# a78-flashcart.net
KiCad netlist of a schematic drawn in EAGLE
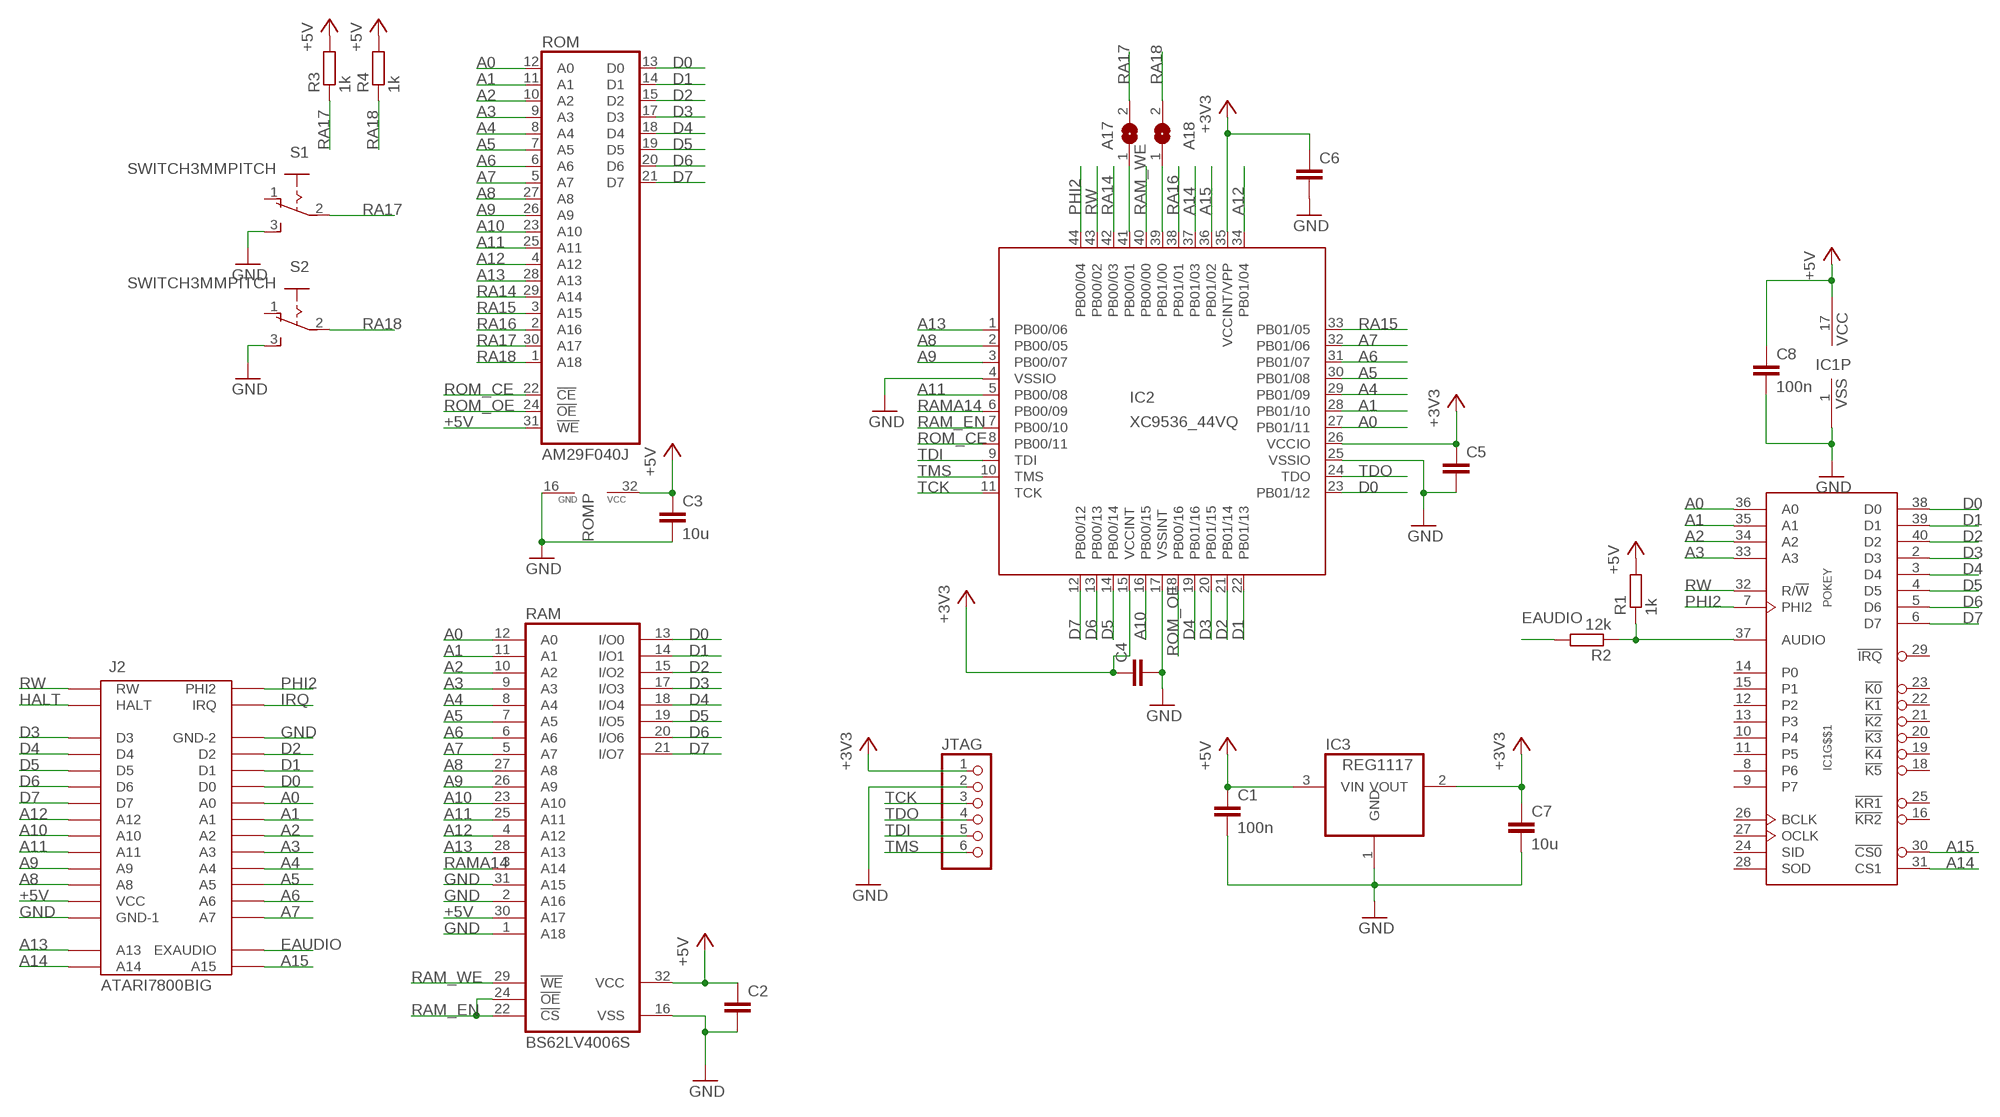
[diagram p0: schematic, sheet 1]

(export (version "E")
  (design (tool "Eeschema 10.0.6"))
  (components
    (comp (ref "A17") (value "SJ") (footprint "eagle-import:SJ") (libsource (lib "eagle-import") (part "SJ")))
    (comp (ref "A18") (value "SJ") (footprint "eagle-import:SJ") (libsource (lib "eagle-import") (part "SJ")))
    (comp (ref "C1")
      (value "100n")
      (footprint "eagle-import:C0805")
      (libsource (lib "eagle-import") (part "C-EUC0805"))
    )
    (comp (ref "C2")
      (value "C-EUC0805")
      (footprint "eagle-import:C0805")
      (libsource (lib "eagle-import") (part "C-EUC0805"))
    )
    (comp (ref "C3")
      (value "10u")
      (footprint "eagle-import:C0805")
      (libsource (lib "eagle-import") (part "C-EUC0805"))
    )
    (comp (ref "C4")
      (value "C-EUC0805")
      (footprint "eagle-import:C0805")
      (libsource (lib "eagle-import") (part "C-EUC0805"))
    )
    (comp (ref "C5")
      (value "C-EUC0805")
      (footprint "eagle-import:C0805")
      (libsource (lib "eagle-import") (part "C-EUC0805"))
    )
    (comp (ref "C6")
      (value "C-EUC0805")
      (footprint "eagle-import:C0805")
      (libsource (lib "eagle-import") (part "C-EUC0805"))
    )
    (comp (ref "C7")
      (value "10u")
      (footprint "eagle-import:C0805")
      (libsource (lib "eagle-import") (part "C-EUC0805"))
    )
    (comp (ref "C8")
      (value "100n")
      (footprint "eagle-import:C0805")
      (libsource (lib "eagle-import") (part "C-EUC0805"))
    )
    (comp (ref "IC1")
      (value "POKEY")
      (footprint "eagle-import:DIL40")
      (libsource (lib "eagle-import") (part "POKEY"))
    )
    (comp (ref "IC2")
      (value "XC9536_44VQ")
      (footprint "eagle-import:SQFP-S-10X10-44")
      (fields (field (name "MPN") "XC9536-15VQG44C"))
      (libsource (lib "eagle-import") (part "XC9536_44VQ"))
    )
    (comp (ref "IC3")
      (value "REG1117")
      (footprint "eagle-import:SOT223")
      (libsource (lib "eagle-import") (part "REG1117"))
    )
    (comp (ref "J2")
      (value "ATARI7800BIG")
      (footprint "eagle-import:ATARI-7800-BIG")
      (libsource (lib "eagle-import") (part "ATARI7800BIG"))
    )
    (comp (ref "JTAG")
      (value "PINHD-1X6")
      (footprint "eagle-import:1X06")
      (libsource (lib "eagle-import") (part "PINHD-1X6"))
    )
    (comp (ref "R1")
      (value "1k")
      (footprint "eagle-import:R0805")
      (libsource (lib "eagle-import") (part "R-EU_R0805"))
    )
    (comp (ref "R2")
      (value "12k")
      (footprint "eagle-import:R0805")
      (libsource (lib "eagle-import") (part "R-EU_R0805"))
    )
    (comp (ref "R3")
      (value "1k")
      (footprint "eagle-import:R0805")
      (libsource (lib "eagle-import") (part "R-EU_R0805"))
    )
    (comp (ref "R4")
      (value "1k")
      (footprint "eagle-import:R0805")
      (libsource (lib "eagle-import") (part "R-EU_R0805"))
    )
    (comp (ref "RAM")
      (value "BS62LV4006S")
      (footprint "eagle-import:SOP-32")
      (libsource (lib "eagle-import") (part "BS62LV4006S"))
    )
    (comp (ref "ROM")
      (value "AM29F040J")
      (footprint "eagle-import:PLCC32R")
      (libsource (lib "eagle-import") (part "AM29F040J"))
    )
    (comp (ref "S1")
      (value "SWITCH3MMPITCH")
      (footprint "eagle-import:SWITCH3MMPITCH")
      (libsource (lib "eagle-import") (part "SWITCH3MMPITCH"))
    )
    (comp (ref "S2")
      (value "SWITCH3MMPITCH")
      (footprint "eagle-import:SWITCH3MMPITCH")
      (libsource (lib "eagle-import") (part "SWITCH3MMPITCH"))
    )
  )
  (nets
    (net (code "1") (name "+3V3") (class "Default")
      (node (ref "C4") (pin "1") (pinfunction "1_1") (pintype "passive"))
      (node (ref "C5") (pin "1") (pinfunction "1_1") (pintype "passive"))
      (node (ref "C6") (pin "1") (pinfunction "1_1") (pintype "passive"))
      (node (ref "C7") (pin "1") (pinfunction "1_1") (pintype "passive"))
      (node (ref "IC2") (pin "15") (pinfunction "VCCINT_15") (pintype "power_in"))
      (node (ref "IC2") (pin "26") (pinfunction "VCCIO_26") (pintype "power_in"))
      (node (ref "IC2") (pin "35") (pinfunction "VCCINT/VPP_35") (pintype "input"))
      (node (ref "IC3") (pin "2") (pinfunction "VOUT_2") (pintype "output"))
      (node (ref "JTAG") (pin "1") (pinfunction "1_1") (pintype "passive"))
    )
    (net (code "2") (name "+5V") (class "Default")
      (node (ref "C1") (pin "1") (pinfunction "1_1") (pintype "passive"))
      (node (ref "C2") (pin "1") (pinfunction "1_1") (pintype "passive"))
      (node (ref "C3") (pin "1") (pinfunction "1_1") (pintype "passive"))
      (node (ref "C8") (pin "1") (pinfunction "1_1") (pintype "passive"))
      (node (ref "IC1") (pin "17") (pinfunction "VCC_17") (pintype "power_in"))
      (node (ref "IC3") (pin "3") (pinfunction "VIN_3") (pintype "input"))
      (node (ref "J2") (pin "13") (pinfunction "VCC_13") (pintype "passive"))
      (node (ref "R1") (pin "2") (pinfunction "2_2") (pintype "passive"))
      (node (ref "R3") (pin "2") (pinfunction "2_2") (pintype "passive"))
      (node (ref "R4") (pin "2") (pinfunction "2_2") (pintype "passive"))
      (node (ref "RAM") (pin "30") (pinfunction "A17_30") (pintype "input"))
      (node (ref "RAM") (pin "32") (pinfunction "VCC_32") (pintype "power_in"))
      (node (ref "ROM") (pin "31") (pinfunction "~{WE}_31") (pintype "input"))
      (node (ref "ROM") (pin "32") (pinfunction "VCC_32") (pintype "power_in"))
    )
    (net (code "3") (name "/A0") (class "Default")
      (node (ref "IC1") (pin "36") (pinfunction "A0_36") (pintype "input"))
      (node (ref "IC2") (pin "27") (pinfunction "PB01/11_27") (pintype "bidirectional"))
      (node (ref "J2") (pin "26") (pinfunction "A0_26") (pintype "passive"))
      (node (ref "RAM") (pin "12") (pinfunction "A0_12") (pintype "input"))
      (node (ref "ROM") (pin "12") (pinfunction "A0_12") (pintype "input"))
    )
    (net (code "4") (name "/A1") (class "Default")
      (node (ref "IC1") (pin "35") (pinfunction "A1_35") (pintype "input"))
      (node (ref "IC2") (pin "28") (pinfunction "PB01/10_28") (pintype "bidirectional"))
      (node (ref "J2") (pin "25") (pinfunction "A1_25") (pintype "passive"))
      (node (ref "RAM") (pin "11") (pinfunction "A1_11") (pintype "input"))
      (node (ref "ROM") (pin "11") (pinfunction "A1_11") (pintype "input"))
    )
    (net (code "5") (name "/A2") (class "Default")
      (node (ref "IC1") (pin "34") (pinfunction "A2_34") (pintype "input"))
      (node (ref "J2") (pin "24") (pinfunction "A2_24") (pintype "passive"))
      (node (ref "RAM") (pin "10") (pinfunction "A2_10") (pintype "input"))
      (node (ref "ROM") (pin "10") (pinfunction "A2_10") (pintype "input"))
    )
    (net (code "6") (name "/A3") (class "Default")
      (node (ref "IC1") (pin "33") (pinfunction "A3_33") (pintype "input"))
      (node (ref "J2") (pin "23") (pinfunction "A3_23") (pintype "passive"))
      (node (ref "RAM") (pin "9") (pinfunction "A3_9") (pintype "input"))
      (node (ref "ROM") (pin "9") (pinfunction "A3_9") (pintype "input"))
    )
    (net (code "7") (name "/A4") (class "Default")
      (node (ref "IC2") (pin "29") (pinfunction "PB01/09_29") (pintype "bidirectional"))
      (node (ref "J2") (pin "22") (pinfunction "A4_22") (pintype "passive"))
      (node (ref "RAM") (pin "8") (pinfunction "A4_8") (pintype "input"))
      (node (ref "ROM") (pin "8") (pinfunction "A4_8") (pintype "input"))
    )
    (net (code "8") (name "/A5") (class "Default")
      (node (ref "IC2") (pin "30") (pinfunction "PB01/08_30") (pintype "bidirectional"))
      (node (ref "J2") (pin "21") (pinfunction "A5_21") (pintype "passive"))
      (node (ref "RAM") (pin "7") (pinfunction "A5_7") (pintype "input"))
      (node (ref "ROM") (pin "7") (pinfunction "A5_7") (pintype "input"))
    )
    (net (code "9") (name "/A6") (class "Default")
      (node (ref "IC2") (pin "31") (pinfunction "PB01/07_31") (pintype "bidirectional"))
      (node (ref "J2") (pin "20") (pinfunction "A6_20") (pintype "passive"))
      (node (ref "RAM") (pin "6") (pinfunction "A6_6") (pintype "input"))
      (node (ref "ROM") (pin "6") (pinfunction "A6_6") (pintype "input"))
    )
    (net (code "10") (name "/A7") (class "Default")
      (node (ref "IC2") (pin "32") (pinfunction "PB01/06_32") (pintype "bidirectional"))
      (node (ref "J2") (pin "19") (pinfunction "A7_19") (pintype "passive"))
      (node (ref "RAM") (pin "5") (pinfunction "A7_5") (pintype "input"))
      (node (ref "ROM") (pin "5") (pinfunction "A7_5") (pintype "input"))
    )
    (net (code "11") (name "/A8") (class "Default")
      (node (ref "IC2") (pin "2") (pinfunction "PB00/05_2") (pintype "bidirectional"))
      (node (ref "J2") (pin "12") (pinfunction "A8_12") (pintype "passive"))
      (node (ref "RAM") (pin "27") (pinfunction "A8_27") (pintype "input"))
      (node (ref "ROM") (pin "27") (pinfunction "A8_27") (pintype "input"))
    )
    (net (code "12") (name "/A9") (class "Default")
      (node (ref "IC2") (pin "3") (pinfunction "PB00/07_3") (pintype "bidirectional"))
      (node (ref "J2") (pin "11") (pinfunction "A9_11") (pintype "passive"))
      (node (ref "RAM") (pin "26") (pinfunction "A9_26") (pintype "input"))
      (node (ref "ROM") (pin "26") (pinfunction "A9_26") (pintype "input"))
    )
    (net (code "13") (name "/A10") (class "Default")
      (node (ref "IC2") (pin "16") (pinfunction "PB00/15_16") (pintype "bidirectional"))
      (node (ref "J2") (pin "9") (pinfunction "A10_9") (pintype "passive"))
      (node (ref "RAM") (pin "23") (pinfunction "A10_23") (pintype "input"))
      (node (ref "ROM") (pin "23") (pinfunction "A10_23") (pintype "input"))
    )
    (net (code "14") (name "/A11") (class "Default")
      (node (ref "IC2") (pin "5") (pinfunction "PB00/08_5") (pintype "bidirectional"))
      (node (ref "J2") (pin "10") (pinfunction "A11_10") (pintype "passive"))
      (node (ref "RAM") (pin "25") (pinfunction "A11_25") (pintype "input"))
      (node (ref "ROM") (pin "25") (pinfunction "A11_25") (pintype "input"))
    )
    (net (code "15") (name "/A12") (class "Default")
      (node (ref "IC2") (pin "34") (pinfunction "PB01/04_34") (pintype "bidirectional"))
      (node (ref "J2") (pin "8") (pinfunction "A12_8") (pintype "passive"))
      (node (ref "RAM") (pin "4") (pinfunction "A12_4") (pintype "input"))
      (node (ref "ROM") (pin "4") (pinfunction "A12_4") (pintype "input"))
    )
    (net (code "16") (name "/A13") (class "Default")
      (node (ref "IC2") (pin "1") (pinfunction "PB00/06_1") (pintype "bidirectional"))
      (node (ref "J2") (pin "15") (pinfunction "A13_15") (pintype "passive"))
      (node (ref "RAM") (pin "28") (pinfunction "A13_28") (pintype "input"))
      (node (ref "ROM") (pin "28") (pinfunction "A13_28") (pintype "input"))
    )
    (net (code "17") (name "/A14") (class "Default")
      (node (ref "IC1") (pin "31") (pinfunction "CS1_31") (pintype "input"))
      (node (ref "IC2") (pin "37") (pinfunction "PB01/03_37") (pintype "bidirectional"))
      (node (ref "J2") (pin "16") (pinfunction "A14_16") (pintype "passive"))
    )
    (net (code "18") (name "/A15") (class "Default")
      (node (ref "IC1") (pin "30") (pinfunction "~{CS0}_30") (pintype "input"))
      (node (ref "IC2") (pin "36") (pinfunction "PB01/02_36") (pintype "bidirectional"))
      (node (ref "J2") (pin "17") (pinfunction "A15_17") (pintype "passive"))
    )
    (net (code "19") (name "/D0") (class "Default")
      (node (ref "IC1") (pin "38") (pinfunction "D0_38") (pintype "output"))
      (node (ref "IC2") (pin "23") (pinfunction "PB01/12_23") (pintype "bidirectional"))
      (node (ref "J2") (pin "27") (pinfunction "D0_27") (pintype "passive"))
      (node (ref "RAM") (pin "13") (pinfunction "I/O0_13") (pintype "bidirectional"))
      (node (ref "ROM") (pin "13") (pinfunction "D0_13") (pintype "tri_state"))
    )
    (net (code "20") (name "/D1") (class "Default")
      (node (ref "IC1") (pin "39") (pinfunction "D1_39") (pintype "output"))
      (node (ref "IC2") (pin "22") (pinfunction "PB01/13_22") (pintype "bidirectional"))
      (node (ref "J2") (pin "28") (pinfunction "D1_28") (pintype "passive"))
      (node (ref "RAM") (pin "14") (pinfunction "I/O1_14") (pintype "bidirectional"))
      (node (ref "ROM") (pin "14") (pinfunction "D1_14") (pintype "tri_state"))
    )
    (net (code "21") (name "/D2") (class "Default")
      (node (ref "IC1") (pin "40") (pinfunction "D2_40") (pintype "output"))
      (node (ref "IC2") (pin "21") (pinfunction "PB01/14_21") (pintype "bidirectional"))
      (node (ref "J2") (pin "29") (pinfunction "D2_29") (pintype "passive"))
      (node (ref "RAM") (pin "15") (pinfunction "I/O2_15") (pintype "bidirectional"))
      (node (ref "ROM") (pin "15") (pinfunction "D2_15") (pintype "tri_state"))
    )
    (net (code "22") (name "/D3") (class "Default")
      (node (ref "IC1") (pin "2") (pinfunction "D3_2") (pintype "output"))
      (node (ref "IC2") (pin "20") (pinfunction "PB01/15_20") (pintype "bidirectional"))
      (node (ref "J2") (pin "3") (pinfunction "D3_3") (pintype "passive"))
      (node (ref "RAM") (pin "17") (pinfunction "I/O3_17") (pintype "bidirectional"))
      (node (ref "ROM") (pin "17") (pinfunction "D3_17") (pintype "tri_state"))
    )
    (net (code "23") (name "/D4") (class "Default")
      (node (ref "IC1") (pin "3") (pinfunction "D4_3") (pintype "output"))
      (node (ref "IC2") (pin "19") (pinfunction "PB01/16_19") (pintype "bidirectional"))
      (node (ref "J2") (pin "4") (pinfunction "D4_4") (pintype "passive"))
      (node (ref "RAM") (pin "18") (pinfunction "I/O4_18") (pintype "bidirectional"))
      (node (ref "ROM") (pin "18") (pinfunction "D4_18") (pintype "tri_state"))
    )
    (net (code "24") (name "/D5") (class "Default")
      (node (ref "IC1") (pin "4") (pinfunction "D5_4") (pintype "output"))
      (node (ref "IC2") (pin "14") (pinfunction "PB00/14_14") (pintype "bidirectional"))
      (node (ref "J2") (pin "5") (pinfunction "D5_5") (pintype "passive"))
      (node (ref "RAM") (pin "19") (pinfunction "I/O5_19") (pintype "bidirectional"))
      (node (ref "ROM") (pin "19") (pinfunction "D5_19") (pintype "tri_state"))
    )
    (net (code "25") (name "/D6") (class "Default")
      (node (ref "IC1") (pin "5") (pinfunction "D6_5") (pintype "output"))
      (node (ref "IC2") (pin "13") (pinfunction "PB00/13_13") (pintype "bidirectional"))
      (node (ref "J2") (pin "6") (pinfunction "D6_6") (pintype "passive"))
      (node (ref "RAM") (pin "20") (pinfunction "I/O6_20") (pintype "bidirectional"))
      (node (ref "ROM") (pin "20") (pinfunction "D6_20") (pintype "tri_state"))
    )
    (net (code "26") (name "/D7") (class "Default")
      (node (ref "IC1") (pin "6") (pinfunction "D7_6") (pintype "output"))
      (node (ref "IC2") (pin "12") (pinfunction "PB00/12_12") (pintype "bidirectional"))
      (node (ref "J2") (pin "7") (pinfunction "D7_7") (pintype "passive"))
      (node (ref "RAM") (pin "21") (pinfunction "I/O7_21") (pintype "bidirectional"))
      (node (ref "ROM") (pin "21") (pinfunction "D7_21") (pintype "tri_state"))
    )
    (net (code "27") (name "/EAUDIO") (class "Default")
      (node (ref "J2") (pin "18") (pinfunction "EXAUDIO_18") (pintype "passive"))
      (node (ref "R2") (pin "2") (pinfunction "2_2") (pintype "passive"))
    )
    (net (code "28") (name "/HALT") (class "Default")
      (node (ref "J2") (pin "2") (pinfunction "HALT_2") (pintype "passive"))
    )
    (net (code "29") (name "/IRQ") (class "Default")
      (node (ref "J2") (pin "31") (pinfunction "IRQ_31") (pintype "passive"))
    )
    (net (code "30") (name "/PHI2") (class "Default")
      (node (ref "IC1") (pin "7") (pinfunction "PHI2_7") (pintype "input"))
      (node (ref "IC2") (pin "44") (pinfunction "PB00/04_44") (pintype "bidirectional"))
      (node (ref "J2") (pin "32") (pinfunction "PHI2_32") (pintype "passive"))
    )
    (net (code "31") (name "/RA14") (class "Default")
      (node (ref "IC2") (pin "42") (pinfunction "PB00/03_42") (pintype "bidirectional"))
      (node (ref "ROM") (pin "29") (pinfunction "A14_29") (pintype "input"))
    )
    (net (code "32") (name "/RA15") (class "Default")
      (node (ref "IC2") (pin "33") (pinfunction "PB01/05_33") (pintype "bidirectional"))
      (node (ref "ROM") (pin "3") (pinfunction "A15_3") (pintype "input"))
    )
    (net (code "33") (name "/RA16") (class "Default")
      (node (ref "IC2") (pin "38") (pinfunction "PB01/01_38") (pintype "bidirectional"))
      (node (ref "ROM") (pin "2") (pinfunction "A16_2") (pintype "input"))
    )
    (net (code "34") (name "/RA17") (class "Default")
      (node (ref "A17") (pin "2") (pinfunction "2_2") (pintype "passive"))
      (node (ref "R3") (pin "1") (pinfunction "1_1") (pintype "passive"))
      (node (ref "ROM") (pin "30") (pinfunction "A17_30") (pintype "input"))
      (node (ref "S1") (pin "2") (pinfunction "P_2") (pintype "passive"))
    )
    (net (code "35") (name "/RA18") (class "Default")
      (node (ref "A18") (pin "2") (pinfunction "2_2") (pintype "passive"))
      (node (ref "R4") (pin "1") (pinfunction "1_1") (pintype "passive"))
      (node (ref "ROM") (pin "1") (pinfunction "A18_1") (pintype "input"))
      (node (ref "S2") (pin "2") (pinfunction "P_2") (pintype "passive"))
    )
    (net (code "36") (name "/RAMA14") (class "Default")
      (node (ref "IC2") (pin "6") (pinfunction "PB00/09_6") (pintype "bidirectional"))
      (node (ref "RAM") (pin "3") (pinfunction "A14_3") (pintype "input"))
    )
    (net (code "37") (name "/RAM_EN") (class "Default")
      (node (ref "IC2") (pin "7") (pinfunction "PB00/10_7") (pintype "bidirectional"))
      (node (ref "RAM") (pin "22") (pinfunction "~{CS}_22") (pintype "input"))
      (node (ref "RAM") (pin "24") (pinfunction "~{OE}_24") (pintype "input"))
    )
    (net (code "38") (name "/RAM_WE") (class "Default")
      (node (ref "IC2") (pin "40") (pinfunction "PB00/00_40") (pintype "bidirectional"))
      (node (ref "RAM") (pin "29") (pinfunction "~{WE}_29") (pintype "input"))
    )
    (net (code "39") (name "/ROM_CE") (class "Default")
      (node (ref "IC2") (pin "8") (pinfunction "PB00/11_8") (pintype "bidirectional"))
      (node (ref "ROM") (pin "22") (pinfunction "~{CE}_22") (pintype "input"))
    )
    (net (code "40") (name "/ROM_OE") (class "Default")
      (node (ref "IC2") (pin "18") (pinfunction "PB00/16_18") (pintype "bidirectional"))
      (node (ref "ROM") (pin "24") (pinfunction "~{OE}_24") (pintype "input"))
    )
    (net (code "41") (name "/RW") (class "Default")
      (node (ref "IC1") (pin "32") (pinfunction "R/~{W}_32") (pintype "input"))
      (node (ref "IC2") (pin "43") (pinfunction "PB00/02_43") (pintype "bidirectional"))
      (node (ref "J2") (pin "1") (pinfunction "RW_1") (pintype "passive"))
    )
    (net (code "42") (name "/TCK") (class "Default")
      (node (ref "IC2") (pin "11") (pinfunction "TCK_11") (pintype "input"))
      (node (ref "JTAG") (pin "3") (pinfunction "3_3") (pintype "passive"))
    )
    (net (code "43") (name "/TDI") (class "Default")
      (node (ref "IC2") (pin "9") (pinfunction "TDI_9") (pintype "input"))
      (node (ref "JTAG") (pin "5") (pinfunction "5_5") (pintype "passive"))
    )
    (net (code "44") (name "/TDO") (class "Default")
      (node (ref "IC2") (pin "24") (pinfunction "TDO_24") (pintype "output"))
      (node (ref "JTAG") (pin "4") (pinfunction "4_4") (pintype "passive"))
    )
    (net (code "45") (name "/TMS") (class "Default")
      (node (ref "IC2") (pin "10") (pinfunction "TMS_10") (pintype "input"))
      (node (ref "JTAG") (pin "6") (pinfunction "6_6") (pintype "passive"))
    )
    (net (code "46") (name "GND") (class "Default")
      (node (ref "C1") (pin "2") (pinfunction "2_2") (pintype "passive"))
      (node (ref "C2") (pin "2") (pinfunction "2_2") (pintype "passive"))
      (node (ref "C3") (pin "2") (pinfunction "2_2") (pintype "passive"))
      (node (ref "C4") (pin "2") (pinfunction "2_2") (pintype "passive"))
      (node (ref "C5") (pin "2") (pinfunction "2_2") (pintype "passive"))
      (node (ref "C6") (pin "2") (pinfunction "2_2") (pintype "passive"))
      (node (ref "C7") (pin "2") (pinfunction "2_2") (pintype "passive"))
      (node (ref "C8") (pin "2") (pinfunction "2_2") (pintype "passive"))
      (node (ref "IC1") (pin "1") (pinfunction "VSS_1") (pintype "power_in"))
      (node (ref "IC2") (pin "17") (pinfunction "VSSINT_17") (pintype "power_in"))
      (node (ref "IC2") (pin "25") (pinfunction "VSSIO_25") (pintype "power_in"))
      (node (ref "IC2") (pin "4") (pinfunction "VSSIO_4") (pintype "power_in"))
      (node (ref "IC3") (pin "1") (pinfunction "GND_1") (pintype "power_in"))
      (node (ref "J2") (pin "14") (pinfunction "GND-1_14") (pintype "passive"))
      (node (ref "J2") (pin "30") (pinfunction "GND-2_30") (pintype "passive"))
      (node (ref "JTAG") (pin "2") (pinfunction "2_2") (pintype "passive"))
      (node (ref "RAM") (pin "1") (pinfunction "A18_1") (pintype "input"))
      (node (ref "RAM") (pin "16") (pinfunction "VSS_16") (pintype "power_in"))
      (node (ref "RAM") (pin "2") (pinfunction "A16_2") (pintype "input"))
      (node (ref "RAM") (pin "31") (pinfunction "A15_31") (pintype "input"))
      (node (ref "ROM") (pin "16") (pinfunction "GND_16") (pintype "power_in"))
      (node (ref "S1") (pin "3") (pinfunction "S_3") (pintype "passive"))
      (node (ref "S2") (pin "3") (pinfunction "S_3") (pintype "passive"))
    )
    (net (code "47") (name "Net-(IC1A-AUDIO)") (class "Default")
      (node (ref "IC1") (pin "37") (pinfunction "AUDIO_37") (pintype "output"))
      (node (ref "R1") (pin "1") (pinfunction "1_1") (pintype "passive"))
      (node (ref "R2") (pin "1") (pinfunction "1_1") (pintype "passive"))
    )
    (net (code "48") (name "Net-(IC2-PB00{slash}01)") (class "Default")
      (node (ref "A17") (pin "1") (pinfunction "1_1") (pintype "passive"))
      (node (ref "IC2") (pin "41") (pinfunction "PB00/01_41") (pintype "bidirectional"))
    )
    (net (code "49") (name "Net-(IC2-PB01{slash}00)") (class "Default")
      (node (ref "A18") (pin "1") (pinfunction "1_1") (pintype "passive"))
      (node (ref "IC2") (pin "39") (pinfunction "PB01/00_39") (pintype "bidirectional"))
    )
    (net (code "50") (name "unconnected-(IC1A-BCLK-Pad26)") (class "Default")
      (node (ref "IC1") (pin "26") (pinfunction "BCLK_26") (pintype "bidirectional"))
    )
    (net (code "51") (name "unconnected-(IC1A-OCLK-Pad27)") (class "Default")
      (node (ref "IC1") (pin "27") (pinfunction "OCLK_27") (pintype "output"))
    )
    (net (code "52") (name "unconnected-(IC1A-P0-Pad14)") (class "Default")
      (node (ref "IC1") (pin "14") (pinfunction "P0_14") (pintype "input"))
    )
    (net (code "53") (name "unconnected-(IC1A-P1-Pad15)") (class "Default")
      (node (ref "IC1") (pin "15") (pinfunction "P1_15") (pintype "input"))
    )
    (net (code "54") (name "unconnected-(IC1A-P2-Pad12)") (class "Default")
      (node (ref "IC1") (pin "12") (pinfunction "P2_12") (pintype "input"))
    )
    (net (code "55") (name "unconnected-(IC1A-P3-Pad13)") (class "Default")
      (node (ref "IC1") (pin "13") (pinfunction "P3_13") (pintype "input"))
    )
    (net (code "56") (name "unconnected-(IC1A-P4-Pad10)") (class "Default")
      (node (ref "IC1") (pin "10") (pinfunction "P4_10") (pintype "input"))
    )
    (net (code "57") (name "unconnected-(IC1A-P5-Pad11)") (class "Default")
      (node (ref "IC1") (pin "11") (pinfunction "P5_11") (pintype "input"))
    )
    (net (code "58") (name "unconnected-(IC1A-P6-Pad8)") (class "Default")
      (node (ref "IC1") (pin "8") (pinfunction "P6_8") (pintype "input"))
    )
    (net (code "59") (name "unconnected-(IC1A-P7-Pad9)") (class "Default")
      (node (ref "IC1") (pin "9") (pinfunction "P7_9") (pintype "input"))
    )
    (net (code "60") (name "unconnected-(IC1A-SID-Pad24)") (class "Default")
      (node (ref "IC1") (pin "24") (pinfunction "SID_24") (pintype "input"))
    )
    (net (code "61") (name "unconnected-(IC1A-SOD-Pad28)") (class "Default")
      (node (ref "IC1") (pin "28") (pinfunction "SOD_28") (pintype "output"))
    )
    (net (code "62") (name "unconnected-(IC1A-~{IRQ}-Pad29)") (class "Default")
      (node (ref "IC1") (pin "29") (pinfunction "~{IRQ}_29") (pintype "output"))
    )
    (net (code "63") (name "unconnected-(IC1A-~{K0}-Pad23)") (class "Default")
      (node (ref "IC1") (pin "23") (pinfunction "~{K0}_23") (pintype "output"))
    )
    (net (code "64") (name "unconnected-(IC1A-~{K1}-Pad22)") (class "Default")
      (node (ref "IC1") (pin "22") (pinfunction "~{K1}_22") (pintype "output"))
    )
    (net (code "65") (name "unconnected-(IC1A-~{K2}-Pad21)") (class "Default")
      (node (ref "IC1") (pin "21") (pinfunction "~{K2}_21") (pintype "output"))
    )
    (net (code "66") (name "unconnected-(IC1A-~{K3}-Pad20)") (class "Default")
      (node (ref "IC1") (pin "20") (pinfunction "~{K3}_20") (pintype "output"))
    )
    (net (code "67") (name "unconnected-(IC1A-~{K4}-Pad19)") (class "Default")
      (node (ref "IC1") (pin "19") (pinfunction "~{K4}_19") (pintype "output"))
    )
    (net (code "68") (name "unconnected-(IC1A-~{K5}-Pad18)") (class "Default")
      (node (ref "IC1") (pin "18") (pinfunction "~{K5}_18") (pintype "output"))
    )
    (net (code "69") (name "unconnected-(IC1A-~{KR1}-Pad25)") (class "Default")
      (node (ref "IC1") (pin "25") (pinfunction "~{KR1}_25") (pintype "input"))
    )
    (net (code "70") (name "unconnected-(IC1A-~{KR2}-Pad16)") (class "Default")
      (node (ref "IC1") (pin "16") (pinfunction "~{KR2}_16") (pintype "input"))
    )
    (net (code "71") (name "unconnected-(S1-O-Pad1)") (class "Default")
      (node (ref "S1") (pin "1") (pinfunction "O_1") (pintype "passive"))
    )
    (net (code "72") (name "unconnected-(S2-O-Pad1)") (class "Default")
      (node (ref "S2") (pin "1") (pinfunction "O_1") (pintype "passive"))
    )
  )
)
